# ArduinoUnoShield.net
KiCad netlist of a schematic drawn in Altium Designer
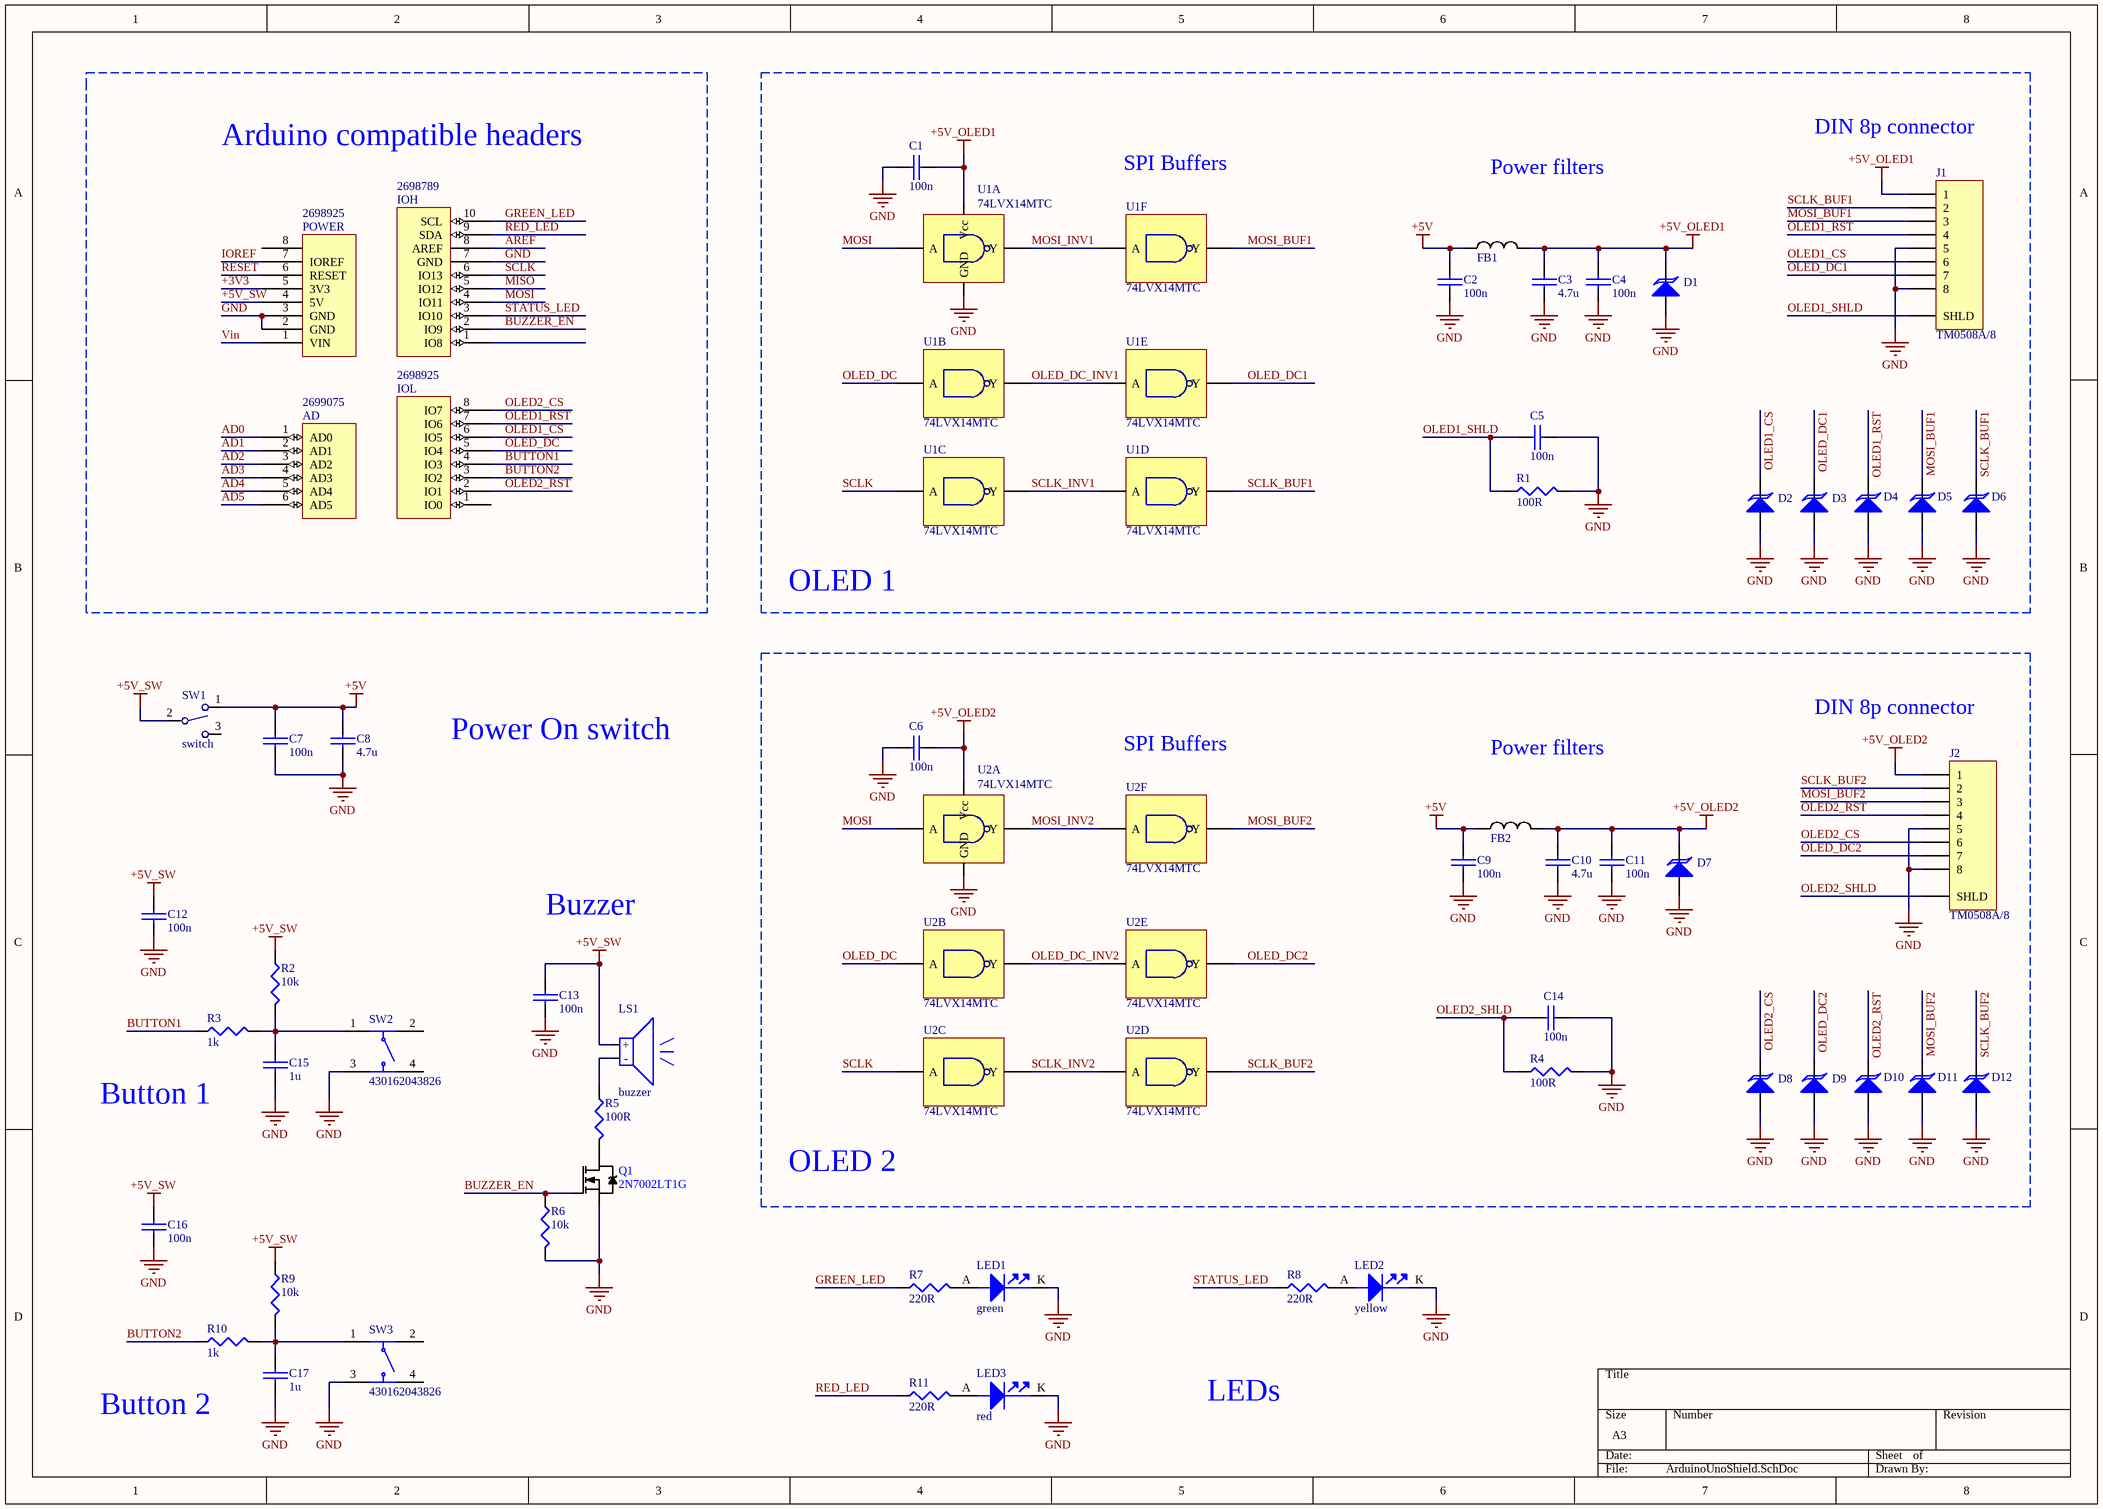
[diagram p0: ArduinoUnoShield.SchDoc]

(export (version "E")
  (design (tool "Eeschema 10.0.6"))
  (components
    (comp (ref "AD")
      (value "AD")
      (footprint "Header:Header 6x1 8.5mm")
      (fields (field (name "SUPPLIER PART NUMBER 4") "2699075"))
      (libsource (lib "Header") (part "AD"))
    )
    (comp (ref "C1")
      (value "100n")
      (footprint "CAPC0402")
      (description "Capacitor: ceramic; MLCC; 100nF; 16V; X7R; ±10%; SMD; 0402")
      (fields (field (name "TOLERANCE") "10%") (field (name "MANUFACTURER") "Murata"))
      (libsource (lib "Capacitors") (part "CAP CER 0402 100n 16V X7R 10%"))
    )
    (comp (ref "C2")
      (value "100n")
      (footprint "CAPC0402")
      (description "Capacitor: ceramic; MLCC; 100nF; 16V; X7R; ±10%; SMD; 0402")
      (fields (field (name "TOLERANCE") "10%") (field (name "MANUFACTURER") "Murata"))
      (libsource (lib "Capacitors") (part "CAP CER 0402 100n 16V X7R 10%"))
    )
    (comp (ref "C3")
      (value "4.7u")
      (footprint "CAPC0603")
      (description "Capacitor: ceramic; MLCC; 4.7uF; 10V; X5R; ±10%; SMD; 0603")
      (fields (field (name "TOLERANCE") "10%") (field (name "MANUFACTURER") "KEMET"))
      (libsource (lib "Capacitors") (part "CAP CER 0603 4.7u 10V X5R 10%"))
    )
    (comp (ref "C4")
      (value "100n")
      (footprint "CAPC0402")
      (description "Capacitor: ceramic; MLCC; 100nF; 16V; X7R; ±10%; SMD; 0402")
      (fields (field (name "TOLERANCE") "10%") (field (name "MANUFACTURER") "Murata"))
      (libsource (lib "Capacitors") (part "CAP CER 0402 100n 16V X7R 10%"))
    )
    (comp (ref "C5")
      (value "100n")
      (footprint "CAPC0402")
      (description "Capacitor: ceramic; MLCC; 100nF; 16V; X7R; ±10%; SMD; 0402")
      (fields (field (name "TOLERANCE") "10%") (field (name "MANUFACTURER") "Murata"))
      (libsource (lib "Capacitors") (part "CAP CER 0402 100n 16V X7R 10%"))
    )
    (comp (ref "C6")
      (value "100n")
      (footprint "CAPC0402")
      (description "Capacitor: ceramic; MLCC; 100nF; 16V; X7R; ±10%; SMD; 0402")
      (fields (field (name "TOLERANCE") "10%") (field (name "MANUFACTURER") "Murata"))
      (libsource (lib "Capacitors") (part "CAP CER 0402 100n 16V X7R 10%"))
    )
    (comp (ref "C7")
      (value "100n")
      (footprint "CAPC0402")
      (description "Capacitor: ceramic; MLCC; 100nF; 16V; X7R; ±10%; SMD; 0402")
      (fields (field (name "TOLERANCE") "10%") (field (name "MANUFACTURER") "Murata"))
      (libsource (lib "Capacitors") (part "CAP CER 0402 100n 16V X7R 10%"))
    )
    (comp (ref "C8")
      (value "4.7u")
      (footprint "CAPC0603")
      (description "Capacitor: ceramic; MLCC; 4.7uF; 10V; X5R; ±10%; SMD; 0603")
      (fields (field (name "TOLERANCE") "10%") (field (name "MANUFACTURER") "KEMET"))
      (libsource (lib "Capacitors") (part "CAP CER 0603 4.7u 10V X5R 10%"))
    )
    (comp (ref "C9")
      (value "100n")
      (footprint "CAPC0402")
      (description "Capacitor: ceramic; MLCC; 100nF; 16V; X7R; ±10%; SMD; 0402")
      (fields (field (name "TOLERANCE") "10%") (field (name "MANUFACTURER") "Murata"))
      (libsource (lib "Capacitors") (part "CAP CER 0402 100n 16V X7R 10%"))
    )
    (comp (ref "C10")
      (value "4.7u")
      (footprint "CAPC0603")
      (description "Capacitor: ceramic; MLCC; 4.7uF; 10V; X5R; ±10%; SMD; 0603")
      (fields (field (name "TOLERANCE") "10%") (field (name "MANUFACTURER") "KEMET"))
      (libsource (lib "Capacitors") (part "CAP CER 0603 4.7u 10V X5R 10%"))
    )
    (comp (ref "C11")
      (value "100n")
      (footprint "CAPC0402")
      (description "Capacitor: ceramic; MLCC; 100nF; 16V; X7R; ±10%; SMD; 0402")
      (fields (field (name "TOLERANCE") "10%") (field (name "MANUFACTURER") "Murata"))
      (libsource (lib "Capacitors") (part "CAP CER 0402 100n 16V X7R 10%"))
    )
    (comp (ref "C12")
      (value "100n")
      (footprint "CAPC0402")
      (description "Capacitor: ceramic; MLCC; 100nF; 16V; X7R; ±10%; SMD; 0402")
      (fields (field (name "TOLERANCE") "10%") (field (name "MANUFACTURER") "Murata"))
      (libsource (lib "Capacitors") (part "CAP CER 0402 100n 16V X7R 10%"))
    )
    (comp (ref "C13")
      (value "100n")
      (footprint "CAPC0402")
      (description "Capacitor: ceramic; MLCC; 100nF; 16V; X7R; ±10%; SMD; 0402")
      (fields (field (name "TOLERANCE") "10%") (field (name "MANUFACTURER") "Murata"))
      (libsource (lib "Capacitors") (part "CAP CER 0402 100n 16V X7R 10%"))
    )
    (comp (ref "C14")
      (value "100n")
      (footprint "CAPC0402")
      (description "Capacitor: ceramic; MLCC; 100nF; 16V; X7R; ±10%; SMD; 0402")
      (fields (field (name "TOLERANCE") "10%") (field (name "MANUFACTURER") "Murata"))
      (libsource (lib "Capacitors") (part "CAP CER 0402 100n 16V X7R 10%"))
    )
    (comp (ref "C15")
      (value "1u")
      (footprint "CAPC0603")
      (description "Capacitor: ceramic; MLCC; 1uF; 10V; X5R; ±10%; SMD; 0603")
      (fields (field (name "TOLERANCE") "10%") (field (name "MANUFACTURER") "Samsung"))
      (libsource (lib "Capacitors") (part "CAP CER 0603 1u 10V X5R 10%"))
    )
    (comp (ref "C16")
      (value "100n")
      (footprint "CAPC0402")
      (description "Capacitor: ceramic; MLCC; 100nF; 16V; X7R; ±10%; SMD; 0402")
      (fields (field (name "TOLERANCE") "10%") (field (name "MANUFACTURER") "Murata"))
      (libsource (lib "Capacitors") (part "CAP CER 0402 100n 16V X7R 10%"))
    )
    (comp (ref "C17")
      (value "1u")
      (footprint "CAPC0603")
      (description "Capacitor: ceramic; MLCC; 1uF; 10V; X5R; ±10%; SMD; 0603")
      (fields (field (name "TOLERANCE") "10%") (field (name "MANUFACTURER") "Samsung"))
      (libsource (lib "Capacitors") (part "CAP CER 0603 1u 10V X5R 10%"))
    )
    (comp (ref "D1")
      (value "ESD9L5.0ST5G")
      (footprint "SOD923")
      (description "Diode: transil; 150mW; 5.4V; unidirectional; SOD923")
      (fields (field (name "MANUFACTURER") "ON Semi"))
      (libsource (lib "Circuit Protection") (part "TVS ESD9L5.0ST5G"))
    )
    (comp (ref "D2")
      (value "ESD9L5.0ST5G")
      (footprint "SOD923")
      (description "Diode: transil; 150mW; 5.4V; unidirectional; SOD923")
      (fields (field (name "MANUFACTURER") "ON Semi"))
      (libsource (lib "Circuit Protection") (part "TVS ESD9L5.0ST5G"))
    )
    (comp (ref "D3")
      (value "ESD9L5.0ST5G")
      (footprint "SOD923")
      (description "Diode: transil; 150mW; 5.4V; unidirectional; SOD923")
      (fields (field (name "MANUFACTURER") "ON Semi"))
      (libsource (lib "Circuit Protection") (part "TVS ESD9L5.0ST5G"))
    )
    (comp (ref "D4")
      (value "ESD9L5.0ST5G")
      (footprint "SOD923")
      (description "Diode: transil; 150mW; 5.4V; unidirectional; SOD923")
      (fields (field (name "MANUFACTURER") "ON Semi"))
      (libsource (lib "Circuit Protection") (part "TVS ESD9L5.0ST5G"))
    )
    (comp (ref "D5")
      (value "ESD9L5.0ST5G")
      (footprint "SOD923")
      (description "Diode: transil; 150mW; 5.4V; unidirectional; SOD923")
      (fields (field (name "MANUFACTURER") "ON Semi"))
      (libsource (lib "Circuit Protection") (part "TVS ESD9L5.0ST5G"))
    )
    (comp (ref "D6")
      (value "ESD9L5.0ST5G")
      (footprint "SOD923")
      (description "Diode: transil; 150mW; 5.4V; unidirectional; SOD923")
      (fields (field (name "MANUFACTURER") "ON Semi"))
      (libsource (lib "Circuit Protection") (part "TVS ESD9L5.0ST5G"))
    )
    (comp (ref "D7")
      (value "ESD9L5.0ST5G")
      (footprint "SOD923")
      (description "Diode: transil; 150mW; 5.4V; unidirectional; SOD923")
      (fields (field (name "MANUFACTURER") "ON Semi"))
      (libsource (lib "Circuit Protection") (part "TVS ESD9L5.0ST5G"))
    )
    (comp (ref "D8")
      (value "ESD9L5.0ST5G")
      (footprint "SOD923")
      (description "Diode: transil; 150mW; 5.4V; unidirectional; SOD923")
      (fields (field (name "MANUFACTURER") "ON Semi"))
      (libsource (lib "Circuit Protection") (part "TVS ESD9L5.0ST5G"))
    )
    (comp (ref "D9")
      (value "ESD9L5.0ST5G")
      (footprint "SOD923")
      (description "Diode: transil; 150mW; 5.4V; unidirectional; SOD923")
      (fields (field (name "MANUFACTURER") "ON Semi"))
      (libsource (lib "Circuit Protection") (part "TVS ESD9L5.0ST5G"))
    )
    (comp (ref "D10")
      (value "ESD9L5.0ST5G")
      (footprint "SOD923")
      (description "Diode: transil; 150mW; 5.4V; unidirectional; SOD923")
      (fields (field (name "MANUFACTURER") "ON Semi"))
      (libsource (lib "Circuit Protection") (part "TVS ESD9L5.0ST5G"))
    )
    (comp (ref "D11")
      (value "ESD9L5.0ST5G")
      (footprint "SOD923")
      (description "Diode: transil; 150mW; 5.4V; unidirectional; SOD923")
      (fields (field (name "MANUFACTURER") "ON Semi"))
      (libsource (lib "Circuit Protection") (part "TVS ESD9L5.0ST5G"))
    )
    (comp (ref "D12")
      (value "ESD9L5.0ST5G")
      (footprint "SOD923")
      (description "Diode: transil; 150mW; 5.4V; unidirectional; SOD923")
      (fields (field (name "MANUFACTURER") "ON Semi"))
      (libsource (lib "Circuit Protection") (part "TVS ESD9L5.0ST5G"))
    )
    (comp (ref "FB1")
      (value "MPZ1005S121C")
      (footprint "RES0402")
      (description "FERRITE BEAD 0402 1.2A 120R@100MHz")
      (fields (field (name "MANUFACTURER") "TDK"))
      (libsource (lib "Filters") (part "FERRITE 0402 1.2A 120R @100MHz"))
    )
    (comp (ref "FB2")
      (value "MPZ1005S121C")
      (footprint "RES0402")
      (description "FERRITE BEAD 0402 1.2A 120R@100MHz")
      (fields (field (name "MANUFACTURER") "TDK"))
      (libsource (lib "Filters") (part "FERRITE 0402 1.2A 120R @100MHz"))
    )
    (comp (ref "IOH")
      (value "IOH")
      (footprint "Header:Header 10x1 8.5mm")
      (fields (field (name "SUPPLIER PART NUMBER 3") "2698789"))
      (libsource (lib "Header") (part "IOH"))
    )
    (comp (ref "IOL")
      (value "IOL")
      (footprint "Header 8x1 8.5mm")
      (fields (field (name "SUPPLIER PART NUMBER 4") "2698925"))
      (libsource (lib "Header") (part "IOL"))
    )
    (comp (ref "J1")
      (value "TM0508A/8")
      (footprint "DIN SOCKET 8P THT")
      (description "Socket; DIN mini; female; PIN:8; shielded; THT; on PCBs; angled 90")
      (fields (field (name "MANUFACTURER") "Lumberg"))
      (libsource (lib "Connectors") (part "DIN MINI SOCKET 8P horizontal THT"))
    )
    (comp (ref "J2")
      (value "TM0508A/8")
      (footprint "DIN SOCKET 8P THT")
      (description "Socket; DIN mini; female; PIN:8; shielded; THT; on PCBs; angled 90")
      (fields (field (name "MANUFACTURER") "Lumberg"))
      (libsource (lib "Connectors") (part "DIN MINI SOCKET 8P horizontal THT"))
    )
    (comp (ref "LED1")
      (value "green")
      (footprint "LED-0603-GREEN")
      (description "LED; SMD; 0603; green; 3-12mcd; 1.6x0.8x0.65mm; 120°; 1.85÷2.5V")
      (fields
        (field (name "MANUFACTURER PART NUMBER") "KPH-1608SGD")
        (field (name "MANUFACTURER") "Kingbright")
      )
      (libsource (lib "Optoelectronics") (part "LED 0603 GREEN MASS"))
    )
    (comp (ref "LED2")
      (value "yellow")
      (footprint "LED-0603-YELLOW")
      (description "LED; SMD; 0603; yellow; 3-8mcd; 1.6x0.8x0.65mm; 120°; 2.1÷2.5V; 20mA")
      (fields
        (field (name "MANUFACTURER PART NUMBER") "KPH-1608YD")
        (field (name "MANUFACTURER") "Kingbright")
      )
      (libsource (lib "Optoelectronics") (part "LED 0603 YELLOW MASS"))
    )
    (comp (ref "LED3")
      (value "red")
      (footprint "LED-0603-RED")
      (description "LED; SMD; 0603; red; 5-12mcd; 1.6x0.8x0.65mm; 120°; 2÷2.5V; 20mA")
      (fields
        (field (name "MANUFACTURER PART NUMBER") "KPH-1608ID")
        (field (name "MANUFACTURER") "Kingbright")
      )
      (libsource (lib "Optoelectronics") (part "LED 0603 RED MASS"))
    )
    (comp (ref "LS1")
      (value "buzzer")
      (footprint "BUZZER DIA 9.5MM H 5MM")
      (description "Elektromagnetic buzzer /w gen; Ø:9.5mm; H:5mm; 5VDC")
      (fields (field (name "MANUFACTURER") "BESTAR") (field (name "MANUFACTURER PART NUMBER") "BMT0905XH05"))
      (libsource (lib "Miscellaneous") (part "BUZZER LBMT0905XH05"))
    )
    (comp (ref "POWER")
      (value "POWER_UNO")
      (footprint "Header 8x1 8.5mm")
      (fields (field (name "SUPPLIER PART NUMBER 4") "2698925"))
      (libsource (lib "Header") (part "POWER_UNO"))
    )
    (comp (ref "Q1")
      (value "2N7002LT1G")
      (footprint "SOT23-3")
      (description "Transistor: N-MOSFET; unipolar; logic level; 60V; 115mA; 225mW")
      (fields (field (name "MANUFACTURER") "ON Semiconductor"))
      (libsource (lib "Transistors") (part "N-MOSFET 2N7002LT1G"))
    )
    (comp (ref "R1")
      (value "100R")
      (footprint "RES0402")
      (description "Resistor: thick film; SMD; 0402; 100R; 63mW; ±1%; -55÷155°C")
      (fields
        (field (name "MANUFACTURER") "Vishay")
        (field (name "MANUFACTURER PART NUMBER") "CRCW0402100RFKTDBC")
      )
      (libsource (lib "Resistors") (part "RES 0402 100R 1% 63mW"))
    )
    (comp (ref "R2")
      (value "10k")
      (footprint "RES0402")
      (description "Resistor: thick film; SMD; 0402; 10k; 63mW; ±1%; -55÷155°C")
      (fields (field (name "MANUFACTURER") "ROHM") (field (name "MANUFACTURER PART NUMBER") "0402WGF1002TCE"))
      (libsource (lib "Resistors") (part "RES 0402 10k 1% 63mW"))
    )
    (comp (ref "R3")
      (value "1k")
      (footprint "RES0402")
      (description "Resistor: thick film; SMD; 0402; 1k; 63mW; ±1%; -55÷155°C")
      (fields
        (field (name "MANUFACTURER") "Vishay")
        (field (name "MANUFACTURER PART NUMBER") "CRCW04021K00FKTDBC")
      )
      (libsource (lib "Resistors") (part "RES 0402 1k 1% 63mW"))
    )
    (comp (ref "R4")
      (value "100R")
      (footprint "RES0402")
      (description "Resistor: thick film; SMD; 0402; 100R; 63mW; ±1%; -55÷155°C")
      (fields
        (field (name "MANUFACTURER") "Vishay")
        (field (name "MANUFACTURER PART NUMBER") "CRCW0402100RFKTDBC")
      )
      (libsource (lib "Resistors") (part "RES 0402 100R 1% 63mW"))
    )
    (comp (ref "R5")
      (value "100R")
      (footprint "RES0402")
      (description "Resistor: thick film; SMD; 0402; 100Ω; 63mW; ±1%; -55÷155°C")
      (fields
        (field (name "MANUFACTURER") "Vishay")
        (field (name "MANUFACTURER PART NUMBER") "CRCW0402100RFKTDBC")
      )
      (libsource (lib "Resistors") (part "RES 0402 100R 1% 63mW"))
    )
    (comp (ref "R6")
      (value "10k")
      (footprint "RES0402 SMALL")
      (description "Resistor: thick film; SMD; 0402; 10k; 63mW; ±1%; -55÷155°C")
      (fields (field (name "MANUFACTURER") "ROHM") (field (name "MANUFACTURER PART NUMBER") "0402WGF1002TCE"))
      (libsource (lib "Resistors") (part "RES 0402 10k 1% 63mW"))
    )
    (comp (ref "R7")
      (value "220R")
      (footprint "RES0402")
      (description "Rezystor: thick film; SMD; 0402; 220R; 63mW; ±1%; -55÷155°C")
      (fields (field (name "MANUFACTURER") "ROHM") (field (name "MANUFACTURER PART NUMBER") "0402WGF2200TCE"))
      (libsource (lib "Resistors") (part "RES 0402 220R 1% 63mW"))
    )
    (comp (ref "R8")
      (value "220R")
      (footprint "RES0402")
      (description "Rezystor: thick film; SMD; 0402; 220R; 63mW; ±1%; -55÷155°C")
      (fields (field (name "MANUFACTURER") "ROHM") (field (name "MANUFACTURER PART NUMBER") "0402WGF2200TCE"))
      (libsource (lib "Resistors") (part "RES 0402 220R 1% 63mW"))
    )
    (comp (ref "R9")
      (value "10k")
      (footprint "RES0402")
      (description "Resistor: thick film; SMD; 0402; 10k; 63mW; ±1%; -55÷155°C")
      (fields (field (name "MANUFACTURER") "ROHM") (field (name "MANUFACTURER PART NUMBER") "0402WGF1002TCE"))
      (libsource (lib "Resistors") (part "RES 0402 10k 1% 63mW"))
    )
    (comp (ref "R10")
      (value "1k")
      (footprint "RES0402")
      (description "Resistor: thick film; SMD; 0402; 1k; 63mW; ±1%; -55÷155°C")
      (fields
        (field (name "MANUFACTURER") "Vishay")
        (field (name "MANUFACTURER PART NUMBER") "CRCW04021K00FKTDBC")
      )
      (libsource (lib "Resistors") (part "RES 0402 1k 1% 63mW"))
    )
    (comp (ref "R11")
      (value "220R")
      (footprint "RES0402")
      (description "Rezystor: thick film; SMD; 0402; 220R; 63mW; ±1%; -55÷155°C")
      (fields (field (name "MANUFACTURER") "ROHM") (field (name "MANUFACTURER PART NUMBER") "0402WGF2200TCE"))
      (libsource (lib "Resistors") (part "RES 0402 220R 1% 63mW"))
    )
    (comp (ref "SW1")
      (value "switch")
      (footprint "SLIDE SWITCH 5MS1S102AM6QE")
      (description "Switch: slide; Positions:2; SPDT; 2A/250VAC; 5A/28VDC; ON-ON")
      (fields (field (name "MANUFACTURER") "TME?") (field (name "MANUFACTURER PART NUMBER") "5MS1S102AM6QE"))
      (libsource (lib "Miscellaneous") (part "SWITCH SLIDE SPDT THT"))
    )
    (comp (ref "SW2")
      (value "430162043826")
      (footprint "4301x20438x6_12*12")
      (description "12x12mm Vertical type, SMD, height 4.3mm, T&R")
      (fields (field (name "MANUFACTURER") "Wurth"))
      (libsource (lib "Miscellaneous") (part "TACTILE SWITCH 12x12mm 430162043826"))
    )
    (comp (ref "SW3")
      (value "430162043826")
      (footprint "4301x20438x6_12*12")
      (description "12x12mm Vertical type, SMD, height 4.3mm, T&R")
      (fields (field (name "MANUFACTURER") "Wurth"))
      (libsource (lib "Miscellaneous") (part "TACTILE SWITCH 12x12mm 430162043826"))
    )
    (comp (ref "U1")
      (value "74LVX14MTC")
      (footprint "TSSOP14")
      (description "C: digital; NOT; Channels:6; Inputs:6; SMD; TSSOP14; Series: LVX")
      (fields (field (name "VOLTAGE") "2 - 3.6V"))
      (libsource (lib "IC Logic") (part "NOT GATE 6CH 74LVX14MTC"))
    )
    (comp (ref "U2")
      (value "74LVX14MTC")
      (footprint "TSSOP14")
      (description "C: digital; NOT; Channels:6; Inputs:6; SMD; TSSOP14; Series: LVX")
      (fields (field (name "VOLTAGE") "2 - 3.6V"))
      (libsource (lib "IC Logic") (part "NOT GATE 6CH 74LVX14MTC"))
    )
  )
  (nets
    (net (code "1") (name "+5V") (class "Default")
      (node (ref "C2") (pin "1") (pinfunction "1_1") (pintype "passive"))
      (node (ref "C7") (pin "1") (pinfunction "1_1") (pintype "passive"))
      (node (ref "C8") (pin "1") (pinfunction "1_1") (pintype "passive"))
      (node (ref "C9") (pin "1") (pinfunction "1_1") (pintype "passive"))
      (node (ref "FB1") (pin "1") (pinfunction "1_1") (pintype "passive"))
      (node (ref "FB2") (pin "1") (pinfunction "1_1") (pintype "passive"))
      (node (ref "SW1") (pin "1") (pintype "passive"))
    )
    (net (code "2") (name "+5V_OLED1") (class "Default")
      (node (ref "C1") (pin "1") (pinfunction "1_1") (pintype "passive"))
      (node (ref "C3") (pin "1") (pinfunction "1_1") (pintype "passive"))
      (node (ref "C4") (pin "1") (pinfunction "1_1") (pintype "passive"))
      (node (ref "D1") (pin "K") (pinfunction "K_K") (pintype "passive"))
      (node (ref "FB1") (pin "2") (pinfunction "2_2") (pintype "passive"))
      (node (ref "J1") (pin "1") (pinfunction "1_1") (pintype "passive"))
      (node (ref "U1") (pin "14") (pinfunction "Vcc_14") (pintype "passive"))
    )
    (net (code "3") (name "+5V_OLED2") (class "Default")
      (node (ref "C10") (pin "1") (pinfunction "1_1") (pintype "passive"))
      (node (ref "C11") (pin "1") (pinfunction "1_1") (pintype "passive"))
      (node (ref "C6") (pin "1") (pinfunction "1_1") (pintype "passive"))
      (node (ref "D7") (pin "K") (pinfunction "K_K") (pintype "passive"))
      (node (ref "FB2") (pin "2") (pinfunction "2_2") (pintype "passive"))
      (node (ref "J2") (pin "1") (pinfunction "1_1") (pintype "passive"))
      (node (ref "U2") (pin "14") (pinfunction "Vcc_14") (pintype "passive"))
    )
    (net (code "4") (name "+5V_SW") (class "Default")
      (node (ref "C12") (pin "1") (pinfunction "1_1") (pintype "passive"))
      (node (ref "C13") (pin "1") (pinfunction "1_1") (pintype "passive"))
      (node (ref "C16") (pin "1") (pinfunction "1_1") (pintype "passive"))
      (node (ref "LS1") (pin "1") (pinfunction "+_1") (pintype "passive"))
      (node (ref "POWER") (pin "4") (pinfunction "5V_4") (pintype "power_in"))
      (node (ref "R2") (pin "1") (pinfunction "1_1") (pintype "passive"))
      (node (ref "R9") (pin "1") (pinfunction "1_1") (pintype "passive"))
      (node (ref "SW1") (pin "2") (pintype "passive"))
    )
    (net (code "5") (name "/+3V3") (class "Default")
      (node (ref "POWER") (pin "5") (pinfunction "3V3_5") (pintype "power_in"))
    )
    (net (code "7") (name "/AD0") (class "Default")
      (node (ref "AD") (pin "1") (pinfunction "AD0_1") (pintype "bidirectional"))
    )
    (net (code "8") (name "/AD1") (class "Default")
      (node (ref "AD") (pin "2") (pinfunction "AD1_2") (pintype "bidirectional"))
    )
    (net (code "9") (name "/AD2") (class "Default")
      (node (ref "AD") (pin "3") (pinfunction "AD2_3") (pintype "bidirectional"))
    )
    (net (code "10") (name "/AD3") (class "Default")
      (node (ref "AD") (pin "4") (pinfunction "AD3_4") (pintype "bidirectional"))
    )
    (net (code "11") (name "/AD4") (class "Default")
      (node (ref "AD") (pin "5") (pinfunction "AD4_5") (pintype "bidirectional"))
    )
    (net (code "12") (name "/AD5") (class "Default")
      (node (ref "AD") (pin "6") (pinfunction "AD5_6") (pintype "bidirectional"))
    )
    (net (code "13") (name "/AREF") (class "Default")
      (node (ref "IOH") (pin "8") (pinfunction "AREF_8") (pintype "passive"))
    )
    (net (code "14") (name "/BUTTON1") (class "Default")
      (node (ref "IOL") (pin "4") (pinfunction "IO3_4") (pintype "bidirectional"))
      (node (ref "R3") (pin "1") (pinfunction "1_1") (pintype "passive"))
    )
    (net (code "15") (name "/BUTTON2") (class "Default")
      (node (ref "IOL") (pin "3") (pinfunction "IO2_3") (pintype "bidirectional"))
      (node (ref "R10") (pin "1") (pinfunction "1_1") (pintype "passive"))
    )
    (net (code "16") (name "/BUZZER_EN") (class "Default")
      (node (ref "IOH") (pin "2") (pinfunction "IO9_2") (pintype "bidirectional"))
      (node (ref "Q1") (pin "1") (pinfunction "G_1") (pintype "passive"))
      (node (ref "R6") (pin "1") (pinfunction "1_1") (pintype "passive"))
    )
    (net (code "17") (name "/GREEN_LED") (class "Default")
      (node (ref "IOH") (pin "10") (pinfunction "SCL_10") (pintype "bidirectional"))
      (node (ref "R7") (pin "1") (pinfunction "1_1") (pintype "passive"))
    )
    (net (code "18") (name "/IOREF") (class "Default")
      (node (ref "POWER") (pin "7") (pinfunction "IOREF_7") (pintype "power_in"))
    )
    (net (code "19") (name "/MISO") (class "Default")
      (node (ref "IOH") (pin "5") (pinfunction "IO12_5") (pintype "bidirectional"))
    )
    (net (code "20") (name "/MOSI") (class "Default")
      (node (ref "IOH") (pin "4") (pinfunction "IO11_4") (pintype "bidirectional"))
      (node (ref "U1") (pin "1") (pinfunction "A_1") (pintype "passive"))
      (node (ref "U2") (pin "1") (pinfunction "A_1") (pintype "passive"))
    )
    (net (code "21") (name "/MOSI_BUF1") (class "Default")
      (node (ref "D5") (pin "K") (pinfunction "K_K") (pintype "passive"))
      (node (ref "J1") (pin "3") (pinfunction "3_3") (pintype "passive"))
      (node (ref "U1") (pin "12") (pinfunction "Y_12") (pintype "passive"))
    )
    (net (code "22") (name "/MOSI_BUF2") (class "Default")
      (node (ref "D11") (pin "K") (pinfunction "K_K") (pintype "passive"))
      (node (ref "J2") (pin "3") (pinfunction "3_3") (pintype "passive"))
      (node (ref "U2") (pin "12") (pinfunction "Y_12") (pintype "passive"))
    )
    (net (code "23") (name "/MOSI_INV1") (class "Default")
      (node (ref "U1") (pin "13") (pinfunction "A_13") (pintype "passive"))
      (node (ref "U1") (pin "2") (pinfunction "Y_2") (pintype "passive"))
    )
    (net (code "24") (name "/MOSI_INV2") (class "Default")
      (node (ref "U2") (pin "13") (pinfunction "A_13") (pintype "passive"))
      (node (ref "U2") (pin "2") (pinfunction "Y_2") (pintype "passive"))
    )
    (net (code "25") (name "/OLED1_CS") (class "Default")
      (node (ref "D2") (pin "K") (pinfunction "K_K") (pintype "passive"))
      (node (ref "IOL") (pin "6") (pinfunction "IO5_6") (pintype "bidirectional"))
      (node (ref "J1") (pin "6") (pinfunction "6_6") (pintype "passive"))
    )
    (net (code "26") (name "/OLED1_RST") (class "Default")
      (node (ref "D4") (pin "K") (pinfunction "K_K") (pintype "passive"))
      (node (ref "IOL") (pin "7") (pinfunction "IO6_7") (pintype "bidirectional"))
      (node (ref "J1") (pin "4") (pinfunction "4_4") (pintype "passive"))
    )
    (net (code "27") (name "/OLED1_SHLD") (class "Default")
      (node (ref "C5") (pin "2") (pinfunction "2_2") (pintype "passive"))
      (node (ref "J1") (pin "0") (pinfunction "SHLD_0") (pintype "passive"))
      (node (ref "R1") (pin "2") (pinfunction "2_2") (pintype "passive"))
    )
    (net (code "28") (name "/OLED2_CS") (class "Default")
      (node (ref "D8") (pin "K") (pinfunction "K_K") (pintype "passive"))
      (node (ref "IOL") (pin "8") (pinfunction "IO7_8") (pintype "bidirectional"))
      (node (ref "J2") (pin "6") (pinfunction "6_6") (pintype "passive"))
    )
    (net (code "29") (name "/OLED2_RST") (class "Default")
      (node (ref "D10") (pin "K") (pinfunction "K_K") (pintype "passive"))
      (node (ref "IOL") (pin "2") (pinfunction "IO1_2") (pintype "bidirectional"))
      (node (ref "J2") (pin "4") (pinfunction "4_4") (pintype "passive"))
    )
    (net (code "30") (name "/OLED2_SHLD") (class "Default")
      (node (ref "C14") (pin "2") (pinfunction "2_2") (pintype "passive"))
      (node (ref "J2") (pin "0") (pinfunction "SHLD_0") (pintype "passive"))
      (node (ref "R4") (pin "2") (pinfunction "2_2") (pintype "passive"))
    )
    (net (code "31") (name "/OLED_DC") (class "Default")
      (node (ref "IOL") (pin "5") (pinfunction "IO4_5") (pintype "bidirectional"))
      (node (ref "U1") (pin "3") (pinfunction "A_3") (pintype "passive"))
      (node (ref "U2") (pin "3") (pinfunction "A_3") (pintype "passive"))
    )
    (net (code "32") (name "/OLED_DC1") (class "Default")
      (node (ref "D3") (pin "K") (pinfunction "K_K") (pintype "passive"))
      (node (ref "J1") (pin "7") (pinfunction "7_7") (pintype "passive"))
      (node (ref "U1") (pin "10") (pinfunction "Y_10") (pintype "passive"))
    )
    (net (code "33") (name "/OLED_DC2") (class "Default")
      (node (ref "D9") (pin "K") (pinfunction "K_K") (pintype "passive"))
      (node (ref "J2") (pin "7") (pinfunction "7_7") (pintype "passive"))
      (node (ref "U2") (pin "10") (pinfunction "Y_10") (pintype "passive"))
    )
    (net (code "34") (name "/OLED_DC_INV1") (class "Default")
      (node (ref "U1") (pin "11") (pinfunction "A_11") (pintype "passive"))
      (node (ref "U1") (pin "4") (pinfunction "Y_4") (pintype "passive"))
    )
    (net (code "35") (name "/OLED_DC_INV2") (class "Default")
      (node (ref "U2") (pin "11") (pinfunction "A_11") (pintype "passive"))
      (node (ref "U2") (pin "4") (pinfunction "Y_4") (pintype "passive"))
    )
    (net (code "36") (name "/RED_LED") (class "Default")
      (node (ref "IOH") (pin "9") (pinfunction "SDA_9") (pintype "bidirectional"))
      (node (ref "R11") (pin "1") (pinfunction "1_1") (pintype "passive"))
    )
    (net (code "37") (name "/RESET") (class "Default")
      (node (ref "POWER") (pin "6") (pinfunction "RESET_6") (pintype "passive"))
    )
    (net (code "38") (name "/SCLK") (class "Default")
      (node (ref "IOH") (pin "6") (pinfunction "IO13_6") (pintype "bidirectional"))
      (node (ref "U1") (pin "5") (pinfunction "A_5") (pintype "passive"))
      (node (ref "U2") (pin "5") (pinfunction "A_5") (pintype "passive"))
    )
    (net (code "39") (name "/SCLK_BUF1") (class "Default")
      (node (ref "D6") (pin "K") (pinfunction "K_K") (pintype "passive"))
      (node (ref "J1") (pin "2") (pinfunction "2_2") (pintype "passive"))
      (node (ref "U1") (pin "9") (pinfunction "Y_9") (pintype "passive"))
    )
    (net (code "40") (name "/SCLK_BUF2") (class "Default")
      (node (ref "D12") (pin "K") (pinfunction "K_K") (pintype "passive"))
      (node (ref "J2") (pin "2") (pinfunction "2_2") (pintype "passive"))
      (node (ref "U2") (pin "9") (pinfunction "Y_9") (pintype "passive"))
    )
    (net (code "41") (name "/SCLK_INV1") (class "Default")
      (node (ref "U1") (pin "6") (pinfunction "Y_6") (pintype "passive"))
      (node (ref "U1") (pin "8") (pinfunction "A_8") (pintype "passive"))
    )
    (net (code "42") (name "/SCLK_INV2") (class "Default")
      (node (ref "U2") (pin "6") (pinfunction "Y_6") (pintype "passive"))
      (node (ref "U2") (pin "8") (pinfunction "A_8") (pintype "passive"))
    )
    (net (code "43") (name "/STATUS_LED") (class "Default")
      (node (ref "IOH") (pin "3") (pinfunction "IO10_3") (pintype "bidirectional"))
      (node (ref "R8") (pin "1") (pinfunction "1_1") (pintype "passive"))
    )
    (net (code "44") (name "/Vin") (class "Default")
      (node (ref "POWER") (pin "1") (pinfunction "VIN_1") (pintype "power_in"))
    )
    (net (code "45") (name "GND") (class "Default")
      (node (ref "C1") (pin "2") (pinfunction "2_2") (pintype "passive"))
      (node (ref "C10") (pin "2") (pinfunction "2_2") (pintype "passive"))
      (node (ref "C11") (pin "2") (pinfunction "2_2") (pintype "passive"))
      (node (ref "C12") (pin "2") (pinfunction "2_2") (pintype "passive"))
      (node (ref "C13") (pin "2") (pinfunction "2_2") (pintype "passive"))
      (node (ref "C14") (pin "1") (pinfunction "1_1") (pintype "passive"))
      (node (ref "C15") (pin "2") (pinfunction "2_2") (pintype "passive"))
      (node (ref "C16") (pin "2") (pinfunction "2_2") (pintype "passive"))
      (node (ref "C17") (pin "2") (pinfunction "2_2") (pintype "passive"))
      (node (ref "C2") (pin "2") (pinfunction "2_2") (pintype "passive"))
      (node (ref "C3") (pin "2") (pinfunction "2_2") (pintype "passive"))
      (node (ref "C4") (pin "2") (pinfunction "2_2") (pintype "passive"))
      (node (ref "C5") (pin "1") (pinfunction "1_1") (pintype "passive"))
      (node (ref "C6") (pin "2") (pinfunction "2_2") (pintype "passive"))
      (node (ref "C7") (pin "2") (pinfunction "2_2") (pintype "passive"))
      (node (ref "C8") (pin "2") (pinfunction "2_2") (pintype "passive"))
      (node (ref "C9") (pin "2") (pinfunction "2_2") (pintype "passive"))
      (node (ref "D1") (pin "A") (pinfunction "A_A") (pintype "passive"))
      (node (ref "D10") (pin "A") (pinfunction "A_A") (pintype "passive"))
      (node (ref "D11") (pin "A") (pinfunction "A_A") (pintype "passive"))
      (node (ref "D12") (pin "A") (pinfunction "A_A") (pintype "passive"))
      (node (ref "D2") (pin "A") (pinfunction "A_A") (pintype "passive"))
      (node (ref "D3") (pin "A") (pinfunction "A_A") (pintype "passive"))
      (node (ref "D4") (pin "A") (pinfunction "A_A") (pintype "passive"))
      (node (ref "D5") (pin "A") (pinfunction "A_A") (pintype "passive"))
      (node (ref "D6") (pin "A") (pinfunction "A_A") (pintype "passive"))
      (node (ref "D7") (pin "A") (pinfunction "A_A") (pintype "passive"))
      (node (ref "D8") (pin "A") (pinfunction "A_A") (pintype "passive"))
      (node (ref "D9") (pin "A") (pinfunction "A_A") (pintype "passive"))
      (node (ref "IOH") (pin "7") (pinfunction "GND_7") (pintype "power_in"))
      (node (ref "J1") (pin "5") (pinfunction "5_5") (pintype "passive"))
      (node (ref "J1") (pin "8") (pinfunction "8_8") (pintype "passive"))
      (node (ref "J2") (pin "5") (pinfunction "5_5") (pintype "passive"))
      (node (ref "J2") (pin "8") (pinfunction "8_8") (pintype "passive"))
      (node (ref "LED1") (pin "K") (pinfunction "CATHODE_K") (pintype "passive"))
      (node (ref "LED2") (pin "K") (pinfunction "CATHODE_K") (pintype "passive"))
      (node (ref "LED3") (pin "K") (pinfunction "CATHODE_K") (pintype "passive"))
      (node (ref "POWER") (pin "2") (pinfunction "GND_2") (pintype "power_in"))
      (node (ref "POWER") (pin "3") (pinfunction "GND_3") (pintype "power_in"))
      (node (ref "Q1") (pin "2") (pinfunction "S_2") (pintype "passive"))
      (node (ref "R1") (pin "1") (pinfunction "1_1") (pintype "passive"))
      (node (ref "R4") (pin "1") (pinfunction "1_1") (pintype "passive"))
      (node (ref "R6") (pin "2") (pinfunction "2_2") (pintype "passive"))
      (node (ref "SW2") (pin "3") (pinfunction "3_3") (pintype "passive"))
      (node (ref "SW3") (pin "3") (pinfunction "3_3") (pintype "passive"))
      (node (ref "U1") (pin "7") (pinfunction "GND_7") (pintype "passive"))
      (node (ref "U2") (pin "7") (pinfunction "GND_7") (pintype "passive"))
    )
    (net (code "46") (name "Net-(C15-Pad1)") (class "Default")
      (node (ref "C15") (pin "1") (pinfunction "1_1") (pintype "passive"))
      (node (ref "R2") (pin "2") (pinfunction "2_2") (pintype "passive"))
      (node (ref "R3") (pin "2") (pinfunction "2_2") (pintype "passive"))
      (node (ref "SW2") (pin "1") (pinfunction "1_1") (pintype "passive"))
    )
    (net (code "47") (name "Net-(C17-Pad1)") (class "Default")
      (node (ref "C17") (pin "1") (pinfunction "1_1") (pintype "passive"))
      (node (ref "R10") (pin "2") (pinfunction "2_2") (pintype "passive"))
      (node (ref "R9") (pin "2") (pinfunction "2_2") (pintype "passive"))
      (node (ref "SW3") (pin "1") (pinfunction "1_1") (pintype "passive"))
    )
    (net (code "48") (name "Net-(LED1-ANODE)") (class "Default")
      (node (ref "LED1") (pin "A") (pinfunction "ANODE_A") (pintype "passive"))
      (node (ref "R7") (pin "2") (pinfunction "2_2") (pintype "passive"))
    )
    (net (code "49") (name "Net-(LED2-ANODE)") (class "Default")
      (node (ref "LED2") (pin "A") (pinfunction "ANODE_A") (pintype "passive"))
      (node (ref "R8") (pin "2") (pinfunction "2_2") (pintype "passive"))
    )
    (net (code "50") (name "Net-(LED3-ANODE)") (class "Default")
      (node (ref "LED3") (pin "A") (pinfunction "ANODE_A") (pintype "passive"))
      (node (ref "R11") (pin "2") (pinfunction "2_2") (pintype "passive"))
    )
    (net (code "51") (name "Net-(LS1--)") (class "Default")
      (node (ref "LS1") (pin "2") (pinfunction "-_2") (pintype "passive"))
      (node (ref "R5") (pin "1") (pinfunction "1_1") (pintype "passive"))
    )
    (net (code "52") (name "Net-(Q1-D)") (class "Default")
      (node (ref "Q1") (pin "3") (pinfunction "D_3") (pintype "passive"))
      (node (ref "R5") (pin "2") (pinfunction "2_2") (pintype "passive"))
    )
    (net (code "53") (name "unconnected-(IOH-IO8-Pad1)") (class "Default")
      (node (ref "IOH") (pin "1") (pinfunction "IO8_1") (pintype "bidirectional"))
    )
    (net (code "54") (name "unconnected-(IOL-IO0-Pad1)") (class "Default")
      (node (ref "IOL") (pin "1") (pinfunction "IO0_1") (pintype "bidirectional"))
    )
    (net (code "55") (name "unconnected-(POWER-Pad8)") (class "Default")
      (node (ref "POWER") (pin "8") (pintype "passive"))
    )
    (net (code "56") (name "unconnected-(SW1-Pad3)") (class "Default")
      (node (ref "SW1") (pin "3") (pintype "passive"))
    )
    (net (code "57") (name "unconnected-(SW2-Pad2)") (class "Default")
      (node (ref "SW2") (pin "2") (pinfunction "2_2") (pintype "passive"))
    )
    (net (code "58") (name "unconnected-(SW2-Pad4)") (class "Default")
      (node (ref "SW2") (pin "4") (pinfunction "4_4") (pintype "passive"))
    )
    (net (code "59") (name "unconnected-(SW3-Pad2)") (class "Default")
      (node (ref "SW3") (pin "2") (pinfunction "2_2") (pintype "passive"))
    )
    (net (code "60") (name "unconnected-(SW3-Pad4)") (class "Default")
      (node (ref "SW3") (pin "4") (pinfunction "4_4") (pintype "passive"))
    )
  )
)
